# 08_-_SD_Card_and_Ethernet.net
KiCad netlist of a schematic drawn in Altium Designer
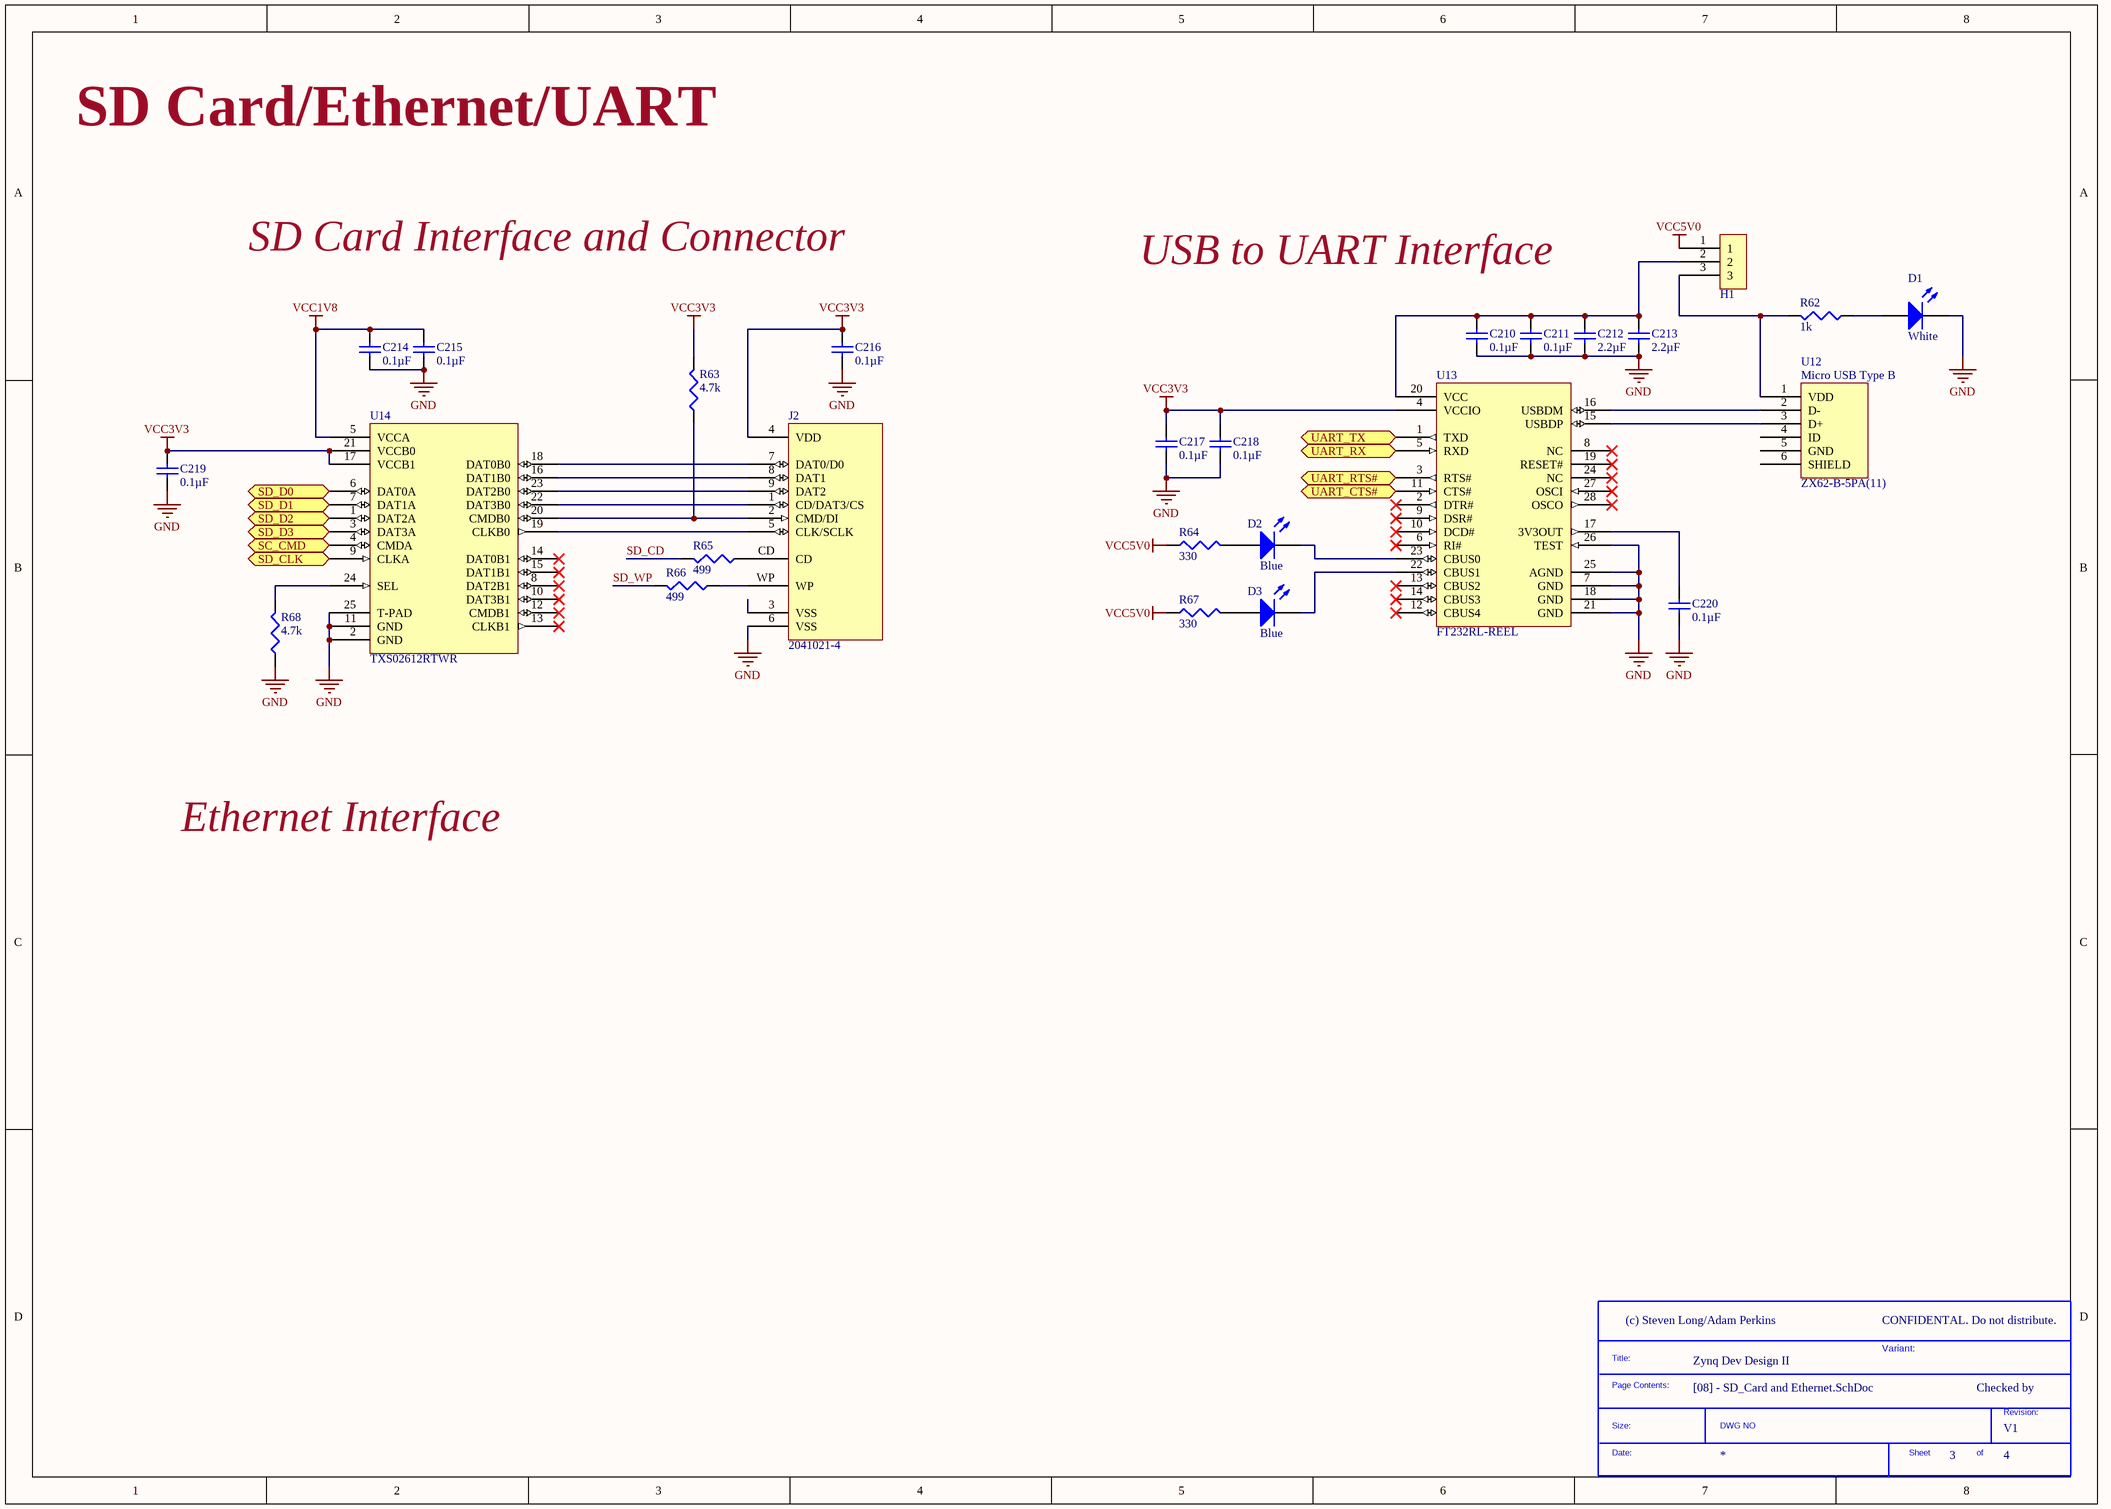
[diagram p0: [08] - SD_Card and Ethernet.SchDoc]

(export (version "E")
  (design (tool "Eeschema 10.0.6"))
  (components
    (comp (ref "C210")
      (value "GRM188R71C104KA01D")
      (footprint "CAP-0603")
      (description "CAP CER 0.1UF 16V X7R 0603")
      (fields
        (field (name "MANUFACTURER") "Murata Electronics North America")
        (field (name "TOLERANCE") "±10%")
        (field (name "CAPACITANCE") "0.1µF")
      )
      (libsource (lib "zynq_dev_V1") (part "GRM188R71C104KA01D"))
    )
    (comp (ref "C211")
      (value "GRM188R71C104KA01D")
      (footprint "CAP-0603")
      (description "CAP CER 0.1UF 16V X7R 0603")
      (fields
        (field (name "MANUFACTURER") "Murata Electronics North America")
        (field (name "TOLERANCE") "±10%")
        (field (name "CAPACITANCE") "0.1µF")
      )
      (libsource (lib "zynq_dev_V1") (part "GRM188R71C104KA01D"))
    )
    (comp (ref "C212")
      (value "GRM188R71A225KE15D")
      (footprint "CAP-0603")
      (description "CAP CER 2.2UF 10V X7R 0603")
      (fields
        (field (name "MANUFACTURER") "Murata Electronics North America")
        (field (name "TOLERANCE") "±10%")
        (field (name "CAPACITANCE") "2.2µF")
      )
      (libsource (lib "zynq_dev_V1") (part "GRM188R71A225KE15D"))
    )
    (comp (ref "C213")
      (value "GRM188R71A225KE15D")
      (footprint "CAP-0603")
      (description "CAP CER 2.2UF 10V X7R 0603")
      (fields
        (field (name "MANUFACTURER") "Murata Electronics North America")
        (field (name "TOLERANCE") "±10%")
        (field (name "CAPACITANCE") "2.2µF")
      )
      (libsource (lib "zynq_dev_V1") (part "GRM188R71A225KE15D"))
    )
    (comp (ref "C214")
      (value "CGA2B1X7R1C104K050BC")
      (footprint "CAP-0402")
      (description "CAP CER 0.1UF 16V X7R 0402")
      (fields
        (field (name "MANUFACTURER") "TDK Corporation")
        (field (name "TOLERANCE") "±10%")
        (field (name "CAPACITANCE") "0.1µF")
      )
      (libsource (lib "zynq_dev_V1") (part "CGA2B1X7R1C104K050BC"))
    )
    (comp (ref "C215")
      (value "CGA2B1X7R1C104K050BC")
      (footprint "CAP-0402")
      (description "CAP CER 0.1UF 16V X7R 0402")
      (fields
        (field (name "MANUFACTURER") "TDK Corporation")
        (field (name "TOLERANCE") "±10%")
        (field (name "CAPACITANCE") "0.1µF")
      )
      (libsource (lib "zynq_dev_V1") (part "CGA2B1X7R1C104K050BC"))
    )
    (comp (ref "C216")
      (value "CGA2B1X7R1C104K050BC")
      (footprint "CAP-0402")
      (description "CAP CER 0.1UF 16V X7R 0402")
      (fields
        (field (name "MANUFACTURER") "TDK Corporation")
        (field (name "TOLERANCE") "±10%")
        (field (name "CAPACITANCE") "0.1µF")
      )
      (libsource (lib "zynq_dev_V1") (part "CGA2B1X7R1C104K050BC"))
    )
    (comp (ref "C217")
      (value "GRM188R71C104KA01D")
      (footprint "CAP-0603")
      (description "CAP CER 0.1UF 16V X7R 0603")
      (fields
        (field (name "MANUFACTURER") "Murata Electronics North America")
        (field (name "TOLERANCE") "±10%")
        (field (name "CAPACITANCE") "0.1µF")
      )
      (libsource (lib "zynq_dev_V1") (part "GRM188R71C104KA01D"))
    )
    (comp (ref "C218")
      (value "GRM188R71C104KA01D")
      (footprint "CAP-0603")
      (description "CAP CER 0.1UF 16V X7R 0603")
      (fields
        (field (name "MANUFACTURER") "Murata Electronics North America")
        (field (name "TOLERANCE") "±10%")
        (field (name "CAPACITANCE") "0.1µF")
      )
      (libsource (lib "zynq_dev_V1") (part "GRM188R71C104KA01D"))
    )
    (comp (ref "C219")
      (value "CGA2B1X7R1C104K050BC")
      (footprint "CAP-0402")
      (description "CAP CER 0.1UF 16V X7R 0402")
      (fields
        (field (name "MANUFACTURER") "TDK Corporation")
        (field (name "TOLERANCE") "±10%")
        (field (name "CAPACITANCE") "0.1µF")
      )
      (libsource (lib "zynq_dev_V1") (part "CGA2B1X7R1C104K050BC"))
    )
    (comp (ref "C220")
      (value "GRM188R71C104KA01D")
      (footprint "CAP-0603")
      (description "CAP CER 0.1UF 16V X7R 0603")
      (fields
        (field (name "MANUFACTURER") "Murata Electronics North America")
        (field (name "TOLERANCE") "±10%")
        (field (name "CAPACITANCE") "0.1µF")
      )
      (libsource (lib "zynq_dev_V1") (part "GRM188R71C104KA01D"))
    )
    (comp (ref "D1")
      (value "SMLE12WBC7W1")
      (description "LED WHITE DIFFUSED 0603 SMD")
      (fields (field (name "MANUFACTURER") "Rohm Semiconductor") (field (name "COLOR") "White"))
      (libsource (lib "zynq_dev_V1") (part "SMLE12WBC7W1"))
    )
    (comp (ref "D2")
      (value "LB Q39E-N1OO-35-1")
      (description "LED BLUE DIFFUSED 0603 SMD")
      (fields (field (name "MANUFACTURER") "OSRAM Opto Semiconductors Inc.") (field (name "COLOR") "Blue"))
      (libsource (lib "zynq_dev_V1") (part "LB Q39E-N1OO-35-1"))
    )
    (comp (ref "D3")
      (value "LB Q39E-N1OO-35-1")
      (description "LED BLUE DIFFUSED 0603 SMD")
      (fields (field (name "MANUFACTURER") "OSRAM Opto Semiconductors Inc.") (field (name "COLOR") "Blue"))
      (libsource (lib "zynq_dev_V1") (part "LB Q39E-N1OO-35-1"))
    )
    (comp (ref "H1")
      (value "68001-203HLF")
      (description "BERGSTIK II .100\" SR STRAIGHT")
      (fields (field (name "MANUFACTURER") "Amphenol FCI"))
      (libsource (lib "zynq_dev_V1") (part "68001-203HLF"))
    )
    (comp (ref "J2")
      (value "2041021-4")
      (description "CONN SD CARD PUSH-PULL R/A SMD")
      (fields (field (name "MANUFACTURER") "TE Connectivity AMP Connectors"))
      (libsource (lib "zynq_dev_V1") (part "2041021-4"))
    )
    (comp (ref "R62")
      (value "ERJ-3EKF1001V")
      (footprint "R0603")
      (description "RES SMD 1K OHM 1% 1/10W 0603")
      (fields
        (field (name "MANUFACTURER") "Panasonic Electronic Components")
        (field (name "TOLERANCE") "±1%")
        (field (name "RESISTANCE (OHMS)") "1k")
      )
      (libsource (lib "zynq_dev_V1") (part "ERJ-3EKF1001V"))
    )
    (comp (ref "R63")
      (value "ERJ-3EKF4701V")
      (footprint "R0603")
      (description "RES SMD 4.7K OHM 1% 1/10W 0603")
      (fields
        (field (name "MANUFACTURER") "Panasonic Electronic Components")
        (field (name "TOLERANCE") "±1%")
        (field (name "RESISTANCE (OHMS)") "4.7k")
      )
      (libsource (lib "zynq_dev_V1") (part "ERJ-3EKF4701V"))
    )
    (comp (ref "R64")
      (value "ERJ-3EKF3300V")
      (footprint "R0603")
      (description "RES SMD 330 OHM 1% 1/10W 0603")
      (fields
        (field (name "MANUFACTURER") "Panasonic Electronic Components")
        (field (name "TOLERANCE") "±1%")
        (field (name "RESISTANCE (OHMS)") "330")
      )
      (libsource (lib "zynq_dev_V1") (part "ERJ-3EKF3300V"))
    )
    (comp (ref "R65")
      (value "ERJ-3EKF4990V")
      (footprint "CAP-0603")
      (description "RES SMD 499 OHM 1% 1/10W 0603")
      (fields
        (field (name "MANUFACTURER") "Panasonic Electronic Components")
        (field (name "TOLERANCE") "±1%")
        (field (name "RESISTANCE (OHMS)") "499")
      )
      (libsource (lib "zynq_dev_V1") (part "ERJ-3EKF4990V"))
    )
    (comp (ref "R66")
      (value "ERJ-3EKF4990V")
      (footprint "CAP-0603")
      (description "RES SMD 499 OHM 1% 1/10W 0603")
      (fields
        (field (name "MANUFACTURER") "Panasonic Electronic Components")
        (field (name "TOLERANCE") "±1%")
        (field (name "RESISTANCE (OHMS)") "499")
      )
      (libsource (lib "zynq_dev_V1") (part "ERJ-3EKF4990V"))
    )
    (comp (ref "R67")
      (value "ERJ-3EKF3300V")
      (footprint "R0603")
      (description "RES SMD 330 OHM 1% 1/10W 0603")
      (fields
        (field (name "MANUFACTURER") "Panasonic Electronic Components")
        (field (name "TOLERANCE") "±1%")
        (field (name "RESISTANCE (OHMS)") "330")
      )
      (libsource (lib "zynq_dev_V1") (part "ERJ-3EKF3300V"))
    )
    (comp (ref "R68")
      (value "ERJ-3EKF4701V")
      (footprint "R0603")
      (description "RES SMD 4.7K OHM 1% 1/10W 0603")
      (fields
        (field (name "MANUFACTURER") "Panasonic Electronic Components")
        (field (name "TOLERANCE") "±1%")
        (field (name "RESISTANCE (OHMS)") "4.7k")
      )
      (libsource (lib "zynq_dev_V1") (part "ERJ-3EKF4701V"))
    )
    (comp (ref "U12")
      (value "ZX62-B-5PA(11)")
      (description "CONN RCPT MICRO USB B SMD R/A")
      (fields (field (name "MANUFACTURER") "Hirose Electric Co Ltd"))
      (libsource (lib "zynq_dev_V1") (part "ZX62-B-5PA(11)"))
    )
    (comp (ref "U13")
      (value "FT232RL-REEL")
      (description "IC USB FS SERIAL UART 28-SSOP")
      (fields (field (name "MANUFACTURER") "FTDI, Future Technology Devices International Ltd"))
      (libsource (lib "zynq_dev_V1") (part "FT232RL-REEL"))
    )
    (comp (ref "U14")
      (value "TXS02612RTWR")
      (description "IC SDIO PORT EXPANDER 24WQFN")
      (fields (field (name "MANUFACTURER") "Texas Instruments"))
      (libsource (lib "zynq_dev_V1") (part "TXS02612RTWR"))
    )
  )
  (nets
    (net (code "1") (name "/SC_CMD") (class "Default")
      (node (ref "U14") (pin "4") (pinfunction "CMDA_4") (pintype "bidirectional"))
    )
    (net (code "2") (name "/SD_CD") (class "Default")
      (node (ref "R65") (pin "2") (pinfunction "2_2") (pintype "passive"))
    )
    (net (code "3") (name "/SD_CLK") (class "Default")
      (node (ref "U14") (pin "9") (pinfunction "CLKA_9") (pintype "input"))
    )
    (net (code "4") (name "/SD_D0") (class "Default")
      (node (ref "U14") (pin "6") (pinfunction "DAT0A_6") (pintype "bidirectional"))
    )
    (net (code "5") (name "/SD_D1") (class "Default")
      (node (ref "U14") (pin "7") (pinfunction "DAT1A_7") (pintype "bidirectional"))
    )
    (net (code "6") (name "/SD_D2") (class "Default")
      (node (ref "U14") (pin "1") (pinfunction "DAT2A_1") (pintype "bidirectional"))
    )
    (net (code "7") (name "/SD_D3") (class "Default")
      (node (ref "U14") (pin "3") (pinfunction "DAT3A_3") (pintype "bidirectional"))
    )
    (net (code "8") (name "/SD_WP") (class "Default")
      (node (ref "R66") (pin "2") (pinfunction "2_2") (pintype "passive"))
    )
    (net (code "9") (name "/UART_CTS#") (class "Default")
      (node (ref "U13") (pin "11") (pinfunction "CTS#_11") (pintype "input"))
    )
    (net (code "10") (name "/UART_RTS#") (class "Default")
      (node (ref "U13") (pin "3") (pinfunction "RTS#_3") (pintype "output"))
    )
    (net (code "11") (name "/UART_RX") (class "Default")
      (node (ref "U13") (pin "5") (pinfunction "RXD_5") (pintype "input"))
    )
    (net (code "12") (name "/UART_TX") (class "Default")
      (node (ref "U13") (pin "1") (pinfunction "TXD_1") (pintype "output"))
    )
    (net (code "13") (name "GND") (class "Default")
      (node (ref "C210") (pin "2") (pinfunction "2_2") (pintype "passive"))
      (node (ref "C211") (pin "2") (pinfunction "2_2") (pintype "passive"))
      (node (ref "C212") (pin "2") (pinfunction "2_2") (pintype "passive"))
      (node (ref "C213") (pin "2") (pinfunction "2_2") (pintype "passive"))
      (node (ref "C214") (pin "2") (pinfunction "2_2") (pintype "passive"))
      (node (ref "C215") (pin "2") (pinfunction "2_2") (pintype "passive"))
      (node (ref "C216") (pin "2") (pinfunction "2_2") (pintype "passive"))
      (node (ref "C217") (pin "2") (pinfunction "2_2") (pintype "passive"))
      (node (ref "C218") (pin "2") (pinfunction "2_2") (pintype "passive"))
      (node (ref "C219") (pin "2") (pinfunction "2_2") (pintype "passive"))
      (node (ref "C220") (pin "2") (pinfunction "2_2") (pintype "passive"))
      (node (ref "D1") (pin "2") (pinfunction "K_2") (pintype "passive"))
      (node (ref "J2") (pin "6") (pinfunction "VSS_6") (pintype "power_in"))
      (node (ref "R68") (pin "1") (pinfunction "1_1") (pintype "passive"))
      (node (ref "U13") (pin "18") (pinfunction "GND_18") (pintype "power_in"))
      (node (ref "U13") (pin "21") (pinfunction "GND_21") (pintype "power_in"))
      (node (ref "U13") (pin "25") (pinfunction "AGND_25") (pintype "power_in"))
      (node (ref "U13") (pin "26") (pinfunction "TEST_26") (pintype "input"))
      (node (ref "U13") (pin "7") (pinfunction "GND_7") (pintype "power_in"))
      (node (ref "U14") (pin "11") (pinfunction "GND_11") (pintype "power_in"))
      (node (ref "U14") (pin "2") (pinfunction "GND_2") (pintype "power_in"))
      (node (ref "U14") (pin "25") (pinfunction "T-PAD_25") (pintype "power_in"))
    )
    (net (code "14") (name "Net-(D1-A)") (class "Default")
      (node (ref "D1") (pin "1") (pinfunction "A_1") (pintype "passive"))
      (node (ref "R62") (pin "1") (pinfunction "1_1") (pintype "passive"))
    )
    (net (code "15") (name "Net-(D2-A)") (class "Default")
      (node (ref "D2") (pin "1") (pinfunction "A_1") (pintype "passive"))
      (node (ref "R64") (pin "2") (pinfunction "2_2") (pintype "passive"))
    )
    (net (code "16") (name "Net-(D2-K)") (class "Default")
      (node (ref "D2") (pin "2") (pinfunction "K_2") (pintype "passive"))
      (node (ref "U13") (pin "23") (pinfunction "CBUS0_23") (pintype "bidirectional"))
    )
    (net (code "17") (name "Net-(D3-A)") (class "Default")
      (node (ref "D3") (pin "1") (pinfunction "A_1") (pintype "passive"))
      (node (ref "R67") (pin "2") (pinfunction "2_2") (pintype "passive"))
    )
    (net (code "18") (name "Net-(D3-K)") (class "Default")
      (node (ref "D3") (pin "2") (pinfunction "K_2") (pintype "passive"))
      (node (ref "U13") (pin "22") (pinfunction "CBUS1_22") (pintype "bidirectional"))
    )
    (net (code "19") (name "Net-(J2-CD{slash}DAT3{slash}CS)") (class "Default")
      (node (ref "J2") (pin "1") (pinfunction "CD/DAT3/CS_1") (pintype "bidirectional"))
      (node (ref "U14") (pin "22") (pinfunction "DAT3B0_22") (pintype "bidirectional"))
    )
    (net (code "20") (name "Net-(J2-CLK{slash}SCLK)") (class "Default")
      (node (ref "J2") (pin "5") (pinfunction "CLK/SCLK_5") (pintype "bidirectional"))
      (node (ref "U14") (pin "19") (pinfunction "CLKB0_19") (pintype "output"))
    )
    (net (code "21") (name "Net-(J2-CMD{slash}DI)") (class "Default")
      (node (ref "J2") (pin "2") (pinfunction "CMD/DI_2") (pintype "input"))
      (node (ref "R63") (pin "1") (pinfunction "1_1") (pintype "passive"))
      (node (ref "U14") (pin "20") (pinfunction "CMDB0_20") (pintype "bidirectional"))
    )
    (net (code "22") (name "Net-(J2-DAT0{slash}D0)") (class "Default")
      (node (ref "J2") (pin "7") (pinfunction "DAT0/D0_7") (pintype "bidirectional"))
      (node (ref "U14") (pin "18") (pinfunction "DAT0B0_18") (pintype "bidirectional"))
    )
    (net (code "23") (name "Net-(J2-DAT1)") (class "Default")
      (node (ref "J2") (pin "8") (pinfunction "DAT1_8") (pintype "bidirectional"))
      (node (ref "U14") (pin "16") (pinfunction "DAT1B0_16") (pintype "bidirectional"))
    )
    (net (code "24") (name "Net-(J2-DAT2)") (class "Default")
      (node (ref "J2") (pin "9") (pinfunction "DAT2_9") (pintype "bidirectional"))
      (node (ref "U14") (pin "23") (pinfunction "DAT2B0_23") (pintype "bidirectional"))
    )
    (net (code "25") (name "Net-(J2-PadCD)") (class "Default")
      (node (ref "J2") (pin "CD") (pinfunction "CD_CD") (pintype "power_in"))
      (node (ref "R65") (pin "1") (pinfunction "1_1") (pintype "passive"))
    )
    (net (code "26") (name "Net-(J2-PadWP)") (class "Default")
      (node (ref "J2") (pin "WP") (pinfunction "WP_WP") (pintype "power_in"))
      (node (ref "R66") (pin "1") (pinfunction "1_1") (pintype "passive"))
    )
    (net (code "27") (name "Net-(U12-D+)") (class "Default")
      (node (ref "U12") (pin "3") (pinfunction "D+_3") (pintype "power_in"))
      (node (ref "U13") (pin "15") (pinfunction "USBDP_15") (pintype "bidirectional"))
    )
    (net (code "28") (name "Net-(U12-D-)") (class "Default")
      (node (ref "U12") (pin "2") (pinfunction "D-_2") (pintype "power_in"))
      (node (ref "U13") (pin "16") (pinfunction "USBDM_16") (pintype "bidirectional"))
    )
    (net (code "29") (name "Net-(U12-VDD)") (class "Default")
      (node (ref "H1") (pin "3") (pinfunction "3_3") (pintype "power_in"))
      (node (ref "R62") (pin "2") (pinfunction "2_2") (pintype "passive"))
      (node (ref "U12") (pin "1") (pinfunction "VDD_1") (pintype "power_in"))
    )
    (net (code "30") (name "Net-(U13-3V3OUT)") (class "Default")
      (node (ref "C220") (pin "1") (pinfunction "1_1") (pintype "passive"))
      (node (ref "U13") (pin "17") (pinfunction "3V3OUT_17") (pintype "output"))
    )
    (net (code "31") (name "Net-(U13-VCC)") (class "Default")
      (node (ref "C210") (pin "1") (pinfunction "1_1") (pintype "passive"))
      (node (ref "C211") (pin "1") (pinfunction "1_1") (pintype "passive"))
      (node (ref "C212") (pin "1") (pinfunction "1_1") (pintype "passive"))
      (node (ref "C213") (pin "1") (pinfunction "1_1") (pintype "passive"))
      (node (ref "H1") (pin "2") (pinfunction "2_2") (pintype "power_in"))
      (node (ref "U13") (pin "20") (pinfunction "VCC_20") (pintype "power_in"))
    )
    (net (code "32") (name "Net-(U14-SEL)") (class "Default")
      (node (ref "R68") (pin "2") (pinfunction "2_2") (pintype "passive"))
      (node (ref "U14") (pin "24") (pinfunction "SEL_24") (pintype "input"))
    )
    (net (code "33") (name "VCC1V8") (class "Default")
      (node (ref "C214") (pin "1") (pinfunction "1_1") (pintype "passive"))
      (node (ref "C215") (pin "1") (pinfunction "1_1") (pintype "passive"))
      (node (ref "U14") (pin "5") (pinfunction "VCCA_5") (pintype "power_in"))
    )
    (net (code "34") (name "VCC3V3") (class "Default")
      (node (ref "C216") (pin "1") (pinfunction "1_1") (pintype "passive"))
      (node (ref "C217") (pin "1") (pinfunction "1_1") (pintype "passive"))
      (node (ref "C218") (pin "1") (pinfunction "1_1") (pintype "passive"))
      (node (ref "C219") (pin "1") (pinfunction "1_1") (pintype "passive"))
      (node (ref "J2") (pin "4") (pinfunction "VDD_4") (pintype "power_in"))
      (node (ref "R63") (pin "2") (pinfunction "2_2") (pintype "passive"))
      (node (ref "U13") (pin "4") (pinfunction "VCCIO_4") (pintype "power_in"))
      (node (ref "U14") (pin "17") (pinfunction "VCCB1_17") (pintype "power_in"))
      (node (ref "U14") (pin "21") (pinfunction "VCCB0_21") (pintype "power_in"))
    )
    (net (code "35") (name "VCC5V0") (class "Default")
      (node (ref "H1") (pin "1") (pinfunction "1_1") (pintype "power_in"))
      (node (ref "R64") (pin "1") (pinfunction "1_1") (pintype "passive"))
      (node (ref "R67") (pin "1") (pinfunction "1_1") (pintype "passive"))
    )
    (net (code "36") (name "unconnected-(J2-VSS-Pad3)") (class "Default")
      (node (ref "J2") (pin "3") (pinfunction "VSS_3") (pintype "power_in"))
    )
    (net (code "37") (name "unconnected-(U12-GND-Pad5)") (class "Default")
      (node (ref "U12") (pin "5") (pinfunction "GND_5") (pintype "power_in"))
    )
    (net (code "38") (name "unconnected-(U12-ID-Pad4)") (class "Default")
      (node (ref "U12") (pin "4") (pinfunction "ID_4") (pintype "power_in"))
    )
    (net (code "39") (name "unconnected-(U12-SHIELD-Pad6)") (class "Default")
      (node (ref "U12") (pin "6") (pinfunction "SHIELD_6") (pintype "power_in"))
    )
    (net (code "40") (name "unconnected-(U13-CBUS2-Pad13)") (class "Default")
      (node (ref "U13") (pin "13") (pinfunction "CBUS2_13") (pintype "bidirectional+no_connect"))
    )
    (net (code "41") (name "unconnected-(U13-CBUS3-Pad14)") (class "Default")
      (node (ref "U13") (pin "14") (pinfunction "CBUS3_14") (pintype "bidirectional+no_connect"))
    )
    (net (code "42") (name "unconnected-(U13-CBUS4-Pad12)") (class "Default")
      (node (ref "U13") (pin "12") (pinfunction "CBUS4_12") (pintype "bidirectional+no_connect"))
    )
    (net (code "43") (name "unconnected-(U13-DCD#-Pad10)") (class "Default")
      (node (ref "U13") (pin "10") (pinfunction "DCD#_10") (pintype "input+no_connect"))
    )
    (net (code "44") (name "unconnected-(U13-DSR#-Pad9)") (class "Default")
      (node (ref "U13") (pin "9") (pinfunction "DSR#_9") (pintype "input+no_connect"))
    )
    (net (code "45") (name "unconnected-(U13-DTR#-Pad2)") (class "Default")
      (node (ref "U13") (pin "2") (pinfunction "DTR#_2") (pintype "output+no_connect"))
    )
    (net (code "46") (name "unconnected-(U13-NC-Pad8)") (class "Default")
      (node (ref "U13") (pin "8") (pinfunction "NC_8") (pintype "power_in+no_connect"))
    )
    (net (code "47") (name "unconnected-(U13-NC-Pad24)") (class "Default")
      (node (ref "U13") (pin "24") (pinfunction "NC_24") (pintype "power_in+no_connect"))
    )
    (net (code "48") (name "unconnected-(U13-OSCI-Pad27)") (class "Default")
      (node (ref "U13") (pin "27") (pinfunction "OSCI_27") (pintype "input+no_connect"))
    )
    (net (code "49") (name "unconnected-(U13-OSCO-Pad28)") (class "Default")
      (node (ref "U13") (pin "28") (pinfunction "OSCO_28") (pintype "output+no_connect"))
    )
    (net (code "50") (name "unconnected-(U13-RESET#-Pad19)") (class "Default")
      (node (ref "U13") (pin "19") (pinfunction "RESET#_19") (pintype "power_in+no_connect"))
    )
    (net (code "51") (name "unconnected-(U13-RI#-Pad6)") (class "Default")
      (node (ref "U13") (pin "6") (pinfunction "RI#_6") (pintype "input+no_connect"))
    )
    (net (code "52") (name "unconnected-(U14-CLKB1-Pad13)") (class "Default")
      (node (ref "U14") (pin "13") (pinfunction "CLKB1_13") (pintype "output+no_connect"))
    )
    (net (code "53") (name "unconnected-(U14-CMDB1-Pad12)") (class "Default")
      (node (ref "U14") (pin "12") (pinfunction "CMDB1_12") (pintype "bidirectional+no_connect"))
    )
    (net (code "54") (name "unconnected-(U14-DAT0B1-Pad14)") (class "Default")
      (node (ref "U14") (pin "14") (pinfunction "DAT0B1_14") (pintype "bidirectional+no_connect"))
    )
    (net (code "55") (name "unconnected-(U14-DAT1B1-Pad15)") (class "Default")
      (node (ref "U14") (pin "15") (pinfunction "DAT1B1_15") (pintype "bidirectional+no_connect"))
    )
    (net (code "56") (name "unconnected-(U14-DAT2B1-Pad8)") (class "Default")
      (node (ref "U14") (pin "8") (pinfunction "DAT2B1_8") (pintype "bidirectional+no_connect"))
    )
    (net (code "57") (name "unconnected-(U14-DAT3B1-Pad10)") (class "Default")
      (node (ref "U14") (pin "10") (pinfunction "DAT3B1_10") (pintype "bidirectional+no_connect"))
    )
  )
)
